# Rear_Motors.net
KiCad netlist of a schematic drawn in Altium Designer
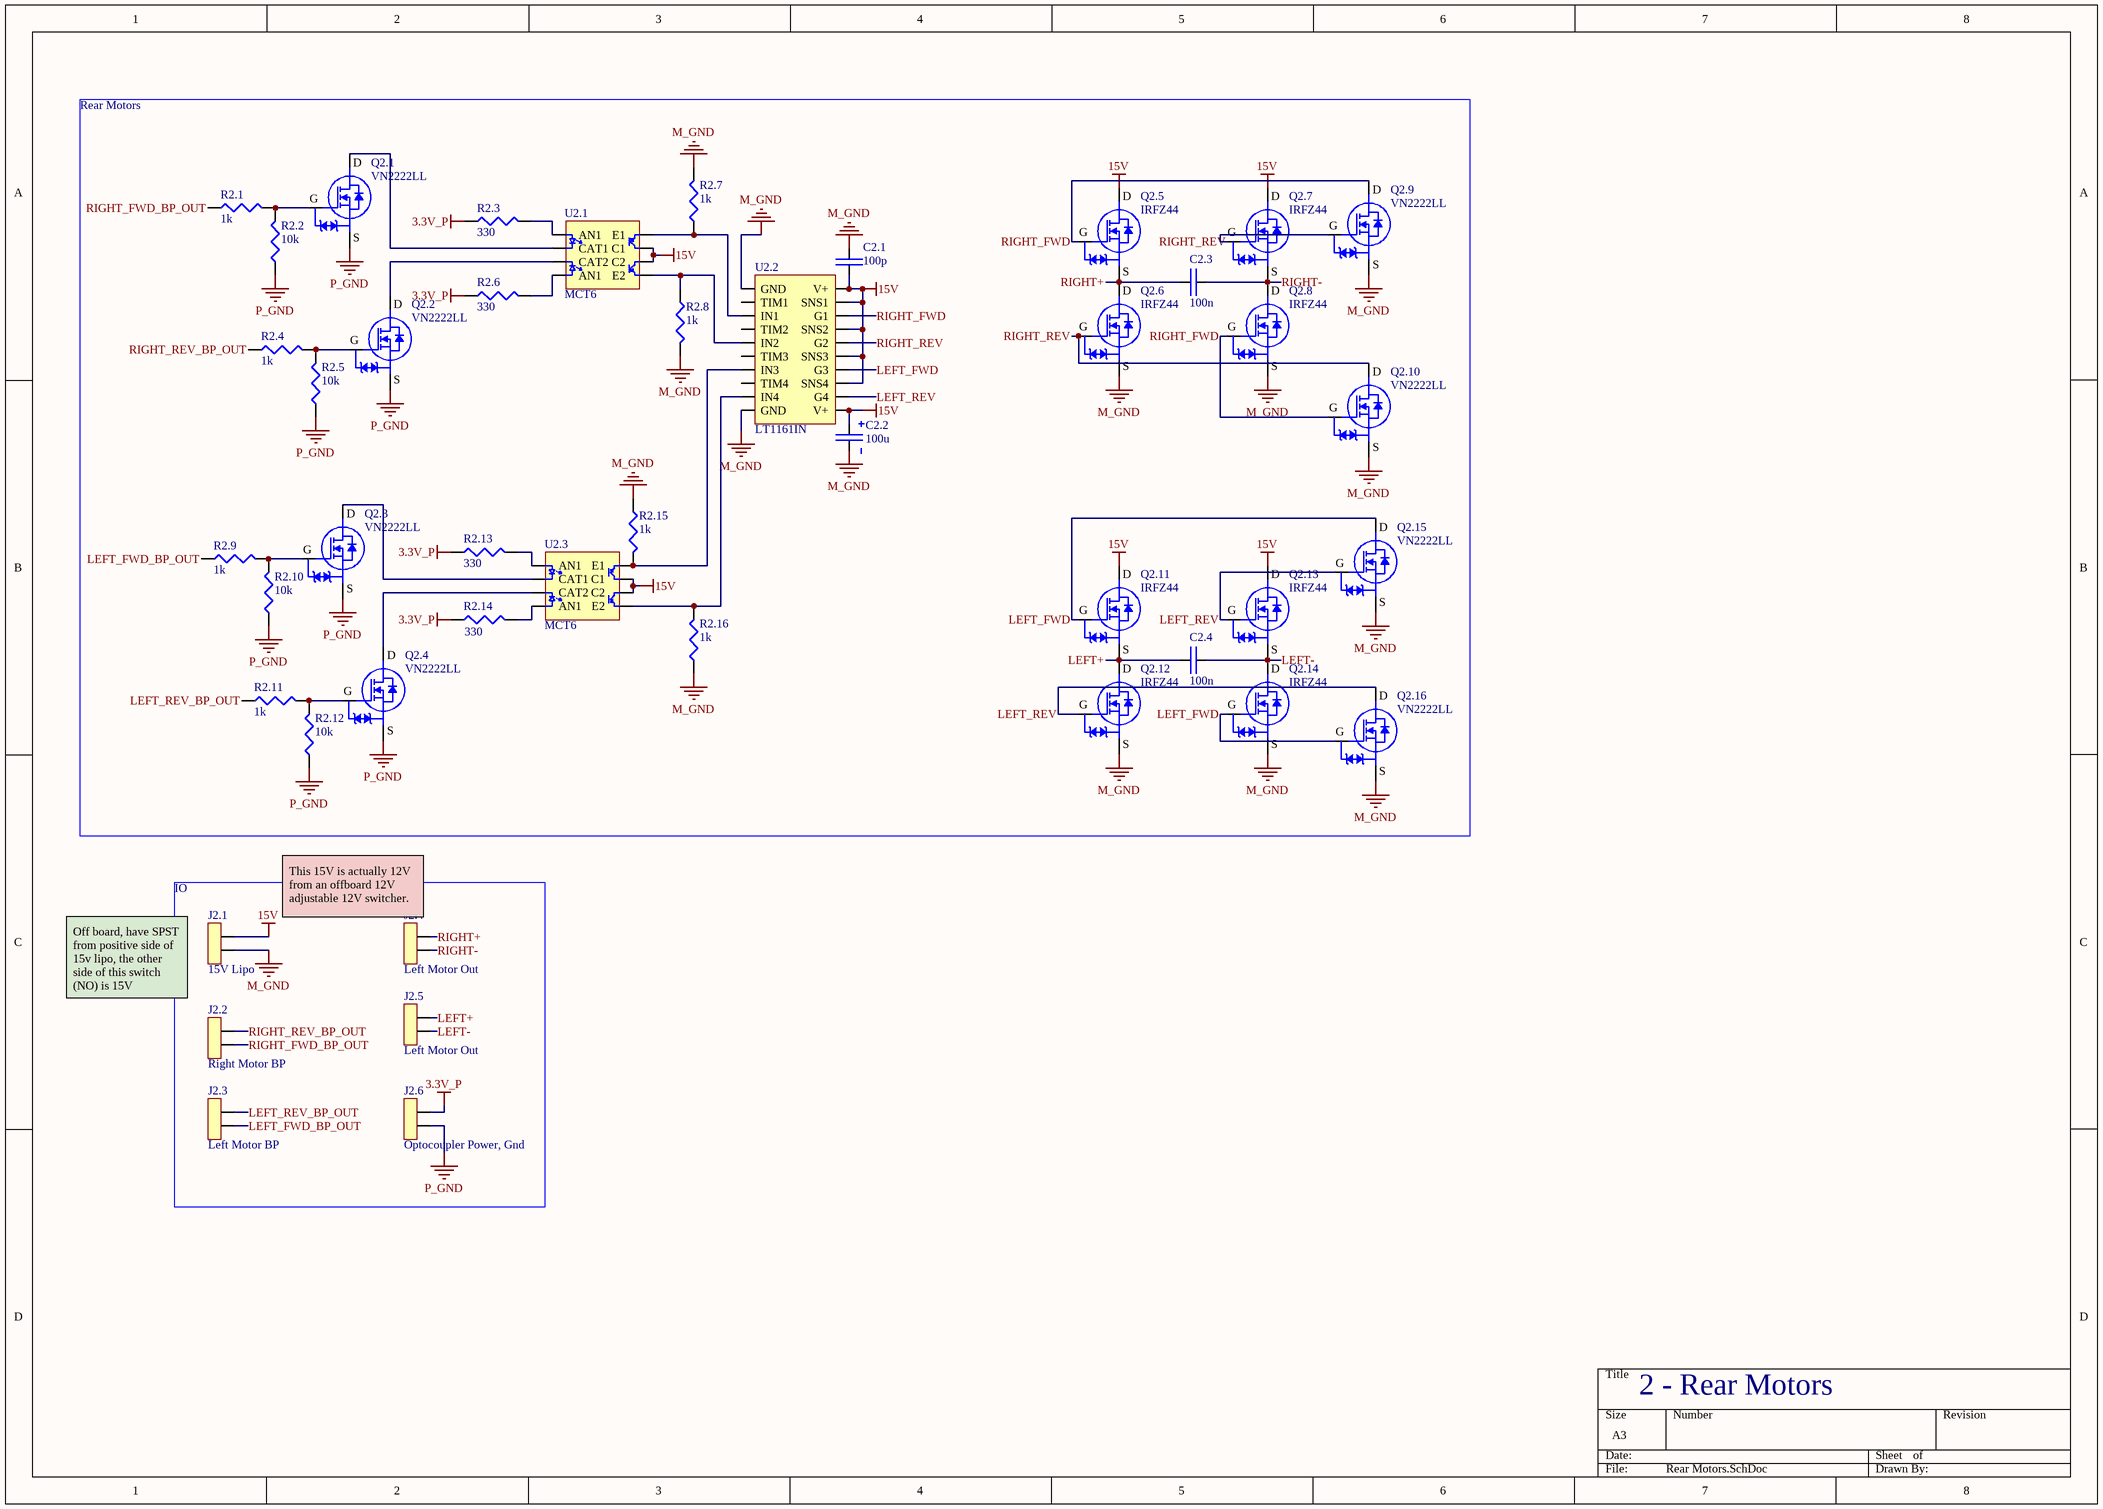
[diagram p0: Rear Motors.SchDoc]

(export (version "E")
  (design (tool "Eeschema 10.0.6"))
  (components
    (comp (ref "C2.1")
      (value "100p")
      (footprint "Non Polarized Cap")
      (libsource (lib "SPICEBot_SchLib") (part "Cap_Generic"))
    )
    (comp (ref "C2.2")
      (value "100u")
      (footprint "Polarized Cap")
      (libsource (lib "SPICEBot_SchLib") (part "Polarized Cap"))
    )
    (comp (ref "C2.3")
      (value "100n")
      (footprint "Non Polarized Cap")
      (libsource (lib "SPICEBot_SchLib") (part "Cap_Generic"))
    )
    (comp (ref "C2.4")
      (value "100n")
      (footprint "Non Polarized Cap")
      (libsource (lib "SPICEBot_SchLib") (part "Cap_Generic"))
    )
    (comp (ref "J2.1")
      (value "15V Lipo")
      (footprint "2pos JST")
      (description "2pos Conn JST")
      (libsource (lib "SPICEBot_SchLib") (part "2pos Conn"))
    )
    (comp (ref "J2.2")
      (value "Right Motor BP")
      (footprint "2pos JST")
      (description "2pos Conn JST")
      (libsource (lib "SPICEBot_SchLib") (part "2pos Conn"))
    )
    (comp (ref "J2.3")
      (value "Left Motor BP")
      (footprint "2pos JST")
      (description "2pos Conn JST")
      (libsource (lib "SPICEBot_SchLib") (part "2pos Conn"))
    )
    (comp (ref "J2.4")
      (value "Left Motor Out")
      (footprint "2pos JST")
      (description "2pos Conn JST")
      (libsource (lib "SPICEBot_SchLib") (part "2pos Conn"))
    )
    (comp (ref "J2.5")
      (value "Left Motor Out")
      (footprint "2pos JST")
      (description "2pos Conn JST")
      (libsource (lib "SPICEBot_SchLib") (part "2pos Conn"))
    )
    (comp (ref "J2.6")
      (value "Optocoupler Power, Gnd")
      (footprint "2pos JST")
      (description "2pos Conn JST")
      (libsource (lib "SPICEBot_SchLib") (part "2pos Conn"))
    )
    (comp (ref "Q2.1")
      (value "VN2222LL")
      (footprint "VN2222LL")
      (description "VN2222LL N-Channel 60 V 150mA 400mW Through Hole TO-92 (TO-226)")
      (libsource (lib "SPICEBot_SchLib") (part "VN2222LL NMOS"))
    )
    (comp (ref "Q2.2")
      (value "VN2222LL")
      (footprint "VN2222LL")
      (description "VN2222LL N-Channel 60 V 150mA 400mW Through Hole TO-92 (TO-226)")
      (libsource (lib "SPICEBot_SchLib") (part "VN2222LL NMOS"))
    )
    (comp (ref "Q2.3")
      (value "VN2222LL")
      (footprint "VN2222LL")
      (description "VN2222LL N-Channel 60 V 150mA 400mW Through Hole TO-92 (TO-226)")
      (libsource (lib "SPICEBot_SchLib") (part "VN2222LL NMOS"))
    )
    (comp (ref "Q2.4")
      (value "VN2222LL")
      (footprint "VN2222LL")
      (description "VN2222LL N-Channel 60 V 150mA 400mW Through Hole TO-92 (TO-226)")
      (libsource (lib "SPICEBot_SchLib") (part "VN2222LL NMOS"))
    )
    (comp (ref "Q2.5")
      (value "IRFZ44")
      (footprint "TO220")
      (description "IRFZ44EPBF N-Channel 60 V 48A 110W Through Hole TO-220AB")
      (libsource (lib "SPICEBot_SchLib") (part "IRFZ44 NMOS"))
    )
    (comp (ref "Q2.6")
      (value "IRFZ44")
      (footprint "TO220")
      (description "IRFZ44EPBF N-Channel 60 V 48A 110W Through Hole TO-220AB")
      (libsource (lib "SPICEBot_SchLib") (part "IRFZ44 NMOS"))
    )
    (comp (ref "Q2.7")
      (value "IRFZ44")
      (footprint "TO220")
      (description "IRFZ44EPBF N-Channel 60 V 48A 110W Through Hole TO-220AB")
      (libsource (lib "SPICEBot_SchLib") (part "IRFZ44 NMOS"))
    )
    (comp (ref "Q2.8")
      (value "IRFZ44")
      (footprint "TO220")
      (description "IRFZ44EPBF N-Channel 60 V 48A 110W Through Hole TO-220AB")
      (libsource (lib "SPICEBot_SchLib") (part "IRFZ44 NMOS"))
    )
    (comp (ref "Q2.9")
      (value "VN2222LL")
      (footprint "VN2222LL")
      (description "VN2222LL N-Channel 60 V 150mA 400mW Through Hole TO-92 (TO-226)")
      (libsource (lib "SPICEBot_SchLib") (part "VN2222LL NMOS"))
    )
    (comp (ref "Q2.10")
      (value "VN2222LL")
      (footprint "VN2222LL")
      (description "VN2222LL N-Channel 60 V 150mA 400mW Through Hole TO-92 (TO-226)")
      (libsource (lib "SPICEBot_SchLib") (part "VN2222LL NMOS"))
    )
    (comp (ref "Q2.11")
      (value "IRFZ44")
      (footprint "TO220")
      (description "IRFZ44EPBF N-Channel 60 V 48A 110W Through Hole TO-220AB")
      (libsource (lib "SPICEBot_SchLib") (part "IRFZ44 NMOS"))
    )
    (comp (ref "Q2.12")
      (value "IRFZ44")
      (footprint "TO220")
      (description "IRFZ44EPBF N-Channel 60 V 48A 110W Through Hole TO-220AB")
      (libsource (lib "SPICEBot_SchLib") (part "IRFZ44 NMOS"))
    )
    (comp (ref "Q2.13")
      (value "IRFZ44")
      (footprint "TO220")
      (description "IRFZ44EPBF N-Channel 60 V 48A 110W Through Hole TO-220AB")
      (libsource (lib "SPICEBot_SchLib") (part "IRFZ44 NMOS"))
    )
    (comp (ref "Q2.14")
      (value "IRFZ44")
      (footprint "TO220")
      (description "IRFZ44EPBF N-Channel 60 V 48A 110W Through Hole TO-220AB")
      (libsource (lib "SPICEBot_SchLib") (part "IRFZ44 NMOS"))
    )
    (comp (ref "Q2.15")
      (value "VN2222LL")
      (footprint "VN2222LL")
      (description "VN2222LL N-Channel 60 V 150mA 400mW Through Hole TO-92 (TO-226)")
      (libsource (lib "SPICEBot_SchLib") (part "VN2222LL NMOS"))
    )
    (comp (ref "Q2.16")
      (value "VN2222LL")
      (footprint "VN2222LL")
      (description "VN2222LL N-Channel 60 V 150mA 400mW Through Hole TO-92 (TO-226)")
      (libsource (lib "SPICEBot_SchLib") (part "VN2222LL NMOS"))
    )
    (comp (ref "R2.1")
      (value "1k")
      (footprint "Res_Generic")
      (libsource (lib "SPICEBot_SchLib") (part "Res_Generic"))
    )
    (comp (ref "R2.2")
      (value "10k")
      (footprint "Res_Generic")
      (libsource (lib "SPICEBot_SchLib") (part "Res_Generic"))
    )
    (comp (ref "R2.3")
      (value "330")
      (footprint "Res_Generic")
      (libsource (lib "SPICEBot_SchLib") (part "Res_Generic"))
    )
    (comp (ref "R2.4")
      (value "1k")
      (footprint "Res_Generic")
      (libsource (lib "SPICEBot_SchLib") (part "Res_Generic"))
    )
    (comp (ref "R2.5")
      (value "10k")
      (footprint "Res_Generic")
      (libsource (lib "SPICEBot_SchLib") (part "Res_Generic"))
    )
    (comp (ref "R2.6")
      (value "330")
      (footprint "Res_Generic")
      (libsource (lib "SPICEBot_SchLib") (part "Res_Generic"))
    )
    (comp (ref "R2.7")
      (value "1k")
      (footprint "Res_Generic")
      (libsource (lib "SPICEBot_SchLib") (part "Res_Generic"))
    )
    (comp (ref "R2.8")
      (value "1k")
      (footprint "Res_Generic")
      (libsource (lib "SPICEBot_SchLib") (part "Res_Generic"))
    )
    (comp (ref "R2.9")
      (value "1k")
      (footprint "Res_Generic")
      (libsource (lib "SPICEBot_SchLib") (part "Res_Generic"))
    )
    (comp (ref "R2.10")
      (value "10k")
      (footprint "Res_Generic")
      (libsource (lib "SPICEBot_SchLib") (part "Res_Generic"))
    )
    (comp (ref "R2.11")
      (value "1k")
      (footprint "Res_Generic")
      (libsource (lib "SPICEBot_SchLib") (part "Res_Generic"))
    )
    (comp (ref "R2.12")
      (value "10k")
      (footprint "Res_Generic")
      (libsource (lib "SPICEBot_SchLib") (part "Res_Generic"))
    )
    (comp (ref "R2.13")
      (value "330")
      (footprint "Res_Generic")
      (libsource (lib "SPICEBot_SchLib") (part "Res_Generic"))
    )
    (comp (ref "R2.14")
      (value "330")
      (footprint "Res_Generic")
      (libsource (lib "SPICEBot_SchLib") (part "Res_Generic"))
    )
    (comp (ref "R2.15")
      (value "1k")
      (footprint "Res_Generic")
      (libsource (lib "SPICEBot_SchLib") (part "Res_Generic"))
    )
    (comp (ref "R2.16")
      (value "1k")
      (footprint "Res_Generic")
      (libsource (lib "SPICEBot_SchLib") (part "Res_Generic"))
    )
    (comp (ref "U2.1")
      (value "MCT6")
      (footprint "DIP8")
      (description "Optoisolator 5.3KV 2CH TRANS 8-DIP")
      (libsource (lib "SPICEBot_SchLib") (part "MCT6 Optocoupler"))
    )
    (comp (ref "U2.2")
      (value "LT1161IN")
      (footprint "DIP20")
      (description "LT1161IN High-Side Gate Driver IC Non-Inverting 20-PDIP")
      (libsource (lib "SPICEBot_SchLib") (part "LT1161IN Gate Driver"))
    )
    (comp (ref "U2.3")
      (value "MCT6")
      (footprint "DIP8")
      (description "Optoisolator 5.3KV 2CH TRANS 8-DIP")
      (libsource (lib "SPICEBot_SchLib") (part "MCT6 Optocoupler"))
    )
  )
  (nets
    (net (code "1") (name "/LEFT+") (class "Default")
      (node (ref "C2.4") (pin "1") (pinfunction "1_1") (pintype "passive"))
      (node (ref "J2.5") (pin "2") (pinfunction "2_2") (pintype "passive"))
      (node (ref "Q2.11") (pin "3") (pinfunction "S_3") (pintype "passive"))
      (node (ref "Q2.12") (pin "2") (pinfunction "D_2") (pintype "passive"))
    )
    (net (code "2") (name "/LEFT-") (class "Default")
      (node (ref "C2.4") (pin "2") (pinfunction "2_2") (pintype "passive"))
      (node (ref "J2.5") (pin "1") (pinfunction "1_1") (pintype "passive"))
      (node (ref "Q2.13") (pin "3") (pinfunction "S_3") (pintype "passive"))
      (node (ref "Q2.14") (pin "2") (pinfunction "D_2") (pintype "passive"))
    )
    (net (code "3") (name "/LEFT_FWD") (class "Default")
      (node (ref "Q2.11") (pin "1") (pinfunction "G_1") (pintype "passive"))
      (node (ref "Q2.14") (pin "1") (pinfunction "G_1") (pintype "passive"))
      (node (ref "Q2.15") (pin "3") (pinfunction "D_3") (pintype "passive"))
      (node (ref "Q2.16") (pin "2") (pinfunction "G_2") (pintype "passive"))
      (node (ref "U2.2") (pin "14") (pinfunction "G3_14") (pintype "passive"))
    )
    (net (code "4") (name "/LEFT_FWD_BP_OUT") (class "Default")
      (node (ref "J2.3") (pin "1") (pinfunction "1_1") (pintype "passive"))
      (node (ref "R2.9") (pin "1") (pinfunction "1_1") (pintype "passive"))
    )
    (net (code "5") (name "/LEFT_REV") (class "Default")
      (node (ref "Q2.12") (pin "1") (pinfunction "G_1") (pintype "passive"))
      (node (ref "Q2.13") (pin "1") (pinfunction "G_1") (pintype "passive"))
      (node (ref "Q2.15") (pin "2") (pinfunction "G_2") (pintype "passive"))
      (node (ref "Q2.16") (pin "3") (pinfunction "D_3") (pintype "passive"))
      (node (ref "U2.2") (pin "12") (pinfunction "G4_12") (pintype "passive"))
    )
    (net (code "6") (name "/LEFT_REV_BP_OUT") (class "Default")
      (node (ref "J2.3") (pin "2") (pinfunction "2_2") (pintype "passive"))
      (node (ref "R2.11") (pin "1") (pinfunction "1_1") (pintype "passive"))
    )
    (net (code "7") (name "/RIGHT+") (class "Default")
      (node (ref "C2.3") (pin "1") (pinfunction "1_1") (pintype "passive"))
      (node (ref "J2.4") (pin "2") (pinfunction "2_2") (pintype "passive"))
      (node (ref "Q2.5") (pin "3") (pinfunction "S_3") (pintype "passive"))
      (node (ref "Q2.6") (pin "2") (pinfunction "D_2") (pintype "passive"))
    )
    (net (code "8") (name "/RIGHT-") (class "Default")
      (node (ref "C2.3") (pin "2") (pinfunction "2_2") (pintype "passive"))
      (node (ref "J2.4") (pin "1") (pinfunction "1_1") (pintype "passive"))
      (node (ref "Q2.7") (pin "3") (pinfunction "S_3") (pintype "passive"))
      (node (ref "Q2.8") (pin "2") (pinfunction "D_2") (pintype "passive"))
    )
    (net (code "9") (name "/RIGHT_FWD") (class "Default")
      (node (ref "Q2.10") (pin "2") (pinfunction "G_2") (pintype "passive"))
      (node (ref "Q2.5") (pin "1") (pinfunction "G_1") (pintype "passive"))
      (node (ref "Q2.8") (pin "1") (pinfunction "G_1") (pintype "passive"))
      (node (ref "Q2.9") (pin "3") (pinfunction "D_3") (pintype "passive"))
      (node (ref "U2.2") (pin "18") (pinfunction "G1_18") (pintype "passive"))
    )
    (net (code "10") (name "/RIGHT_FWD_BP_OUT") (class "Default")
      (node (ref "J2.2") (pin "1") (pinfunction "1_1") (pintype "passive"))
      (node (ref "R2.1") (pin "1") (pinfunction "1_1") (pintype "passive"))
    )
    (net (code "11") (name "/RIGHT_REV") (class "Default")
      (node (ref "Q2.10") (pin "3") (pinfunction "D_3") (pintype "passive"))
      (node (ref "Q2.6") (pin "1") (pinfunction "G_1") (pintype "passive"))
      (node (ref "Q2.7") (pin "1") (pinfunction "G_1") (pintype "passive"))
      (node (ref "Q2.9") (pin "2") (pinfunction "G_2") (pintype "passive"))
      (node (ref "U2.2") (pin "16") (pinfunction "G2_16") (pintype "passive"))
    )
    (net (code "12") (name "/RIGHT_REV_BP_OUT") (class "Default")
      (node (ref "J2.2") (pin "2") (pinfunction "2_2") (pintype "passive"))
      (node (ref "R2.4") (pin "1") (pinfunction "1_1") (pintype "passive"))
    )
    (net (code "13") (name "3.3V_P") (class "Default")
      (node (ref "J2.6") (pin "2") (pinfunction "2_2") (pintype "passive"))
      (node (ref "R2.13") (pin "1") (pinfunction "1_1") (pintype "passive"))
      (node (ref "R2.14") (pin "1") (pinfunction "1_1") (pintype "passive"))
      (node (ref "R2.3") (pin "1") (pinfunction "1_1") (pintype "passive"))
      (node (ref "R2.6") (pin "1") (pinfunction "1_1") (pintype "passive"))
    )
    (net (code "14") (name "15V") (class "Default")
      (node (ref "C2.1") (pin "1") (pinfunction "1_1") (pintype "passive"))
      (node (ref "C2.2") (pin "1") (pinfunction "1_1") (pintype "passive"))
      (node (ref "J2.1") (pin "2") (pinfunction "2_2") (pintype "passive"))
      (node (ref "Q2.11") (pin "2") (pinfunction "D_2") (pintype "passive"))
      (node (ref "Q2.13") (pin "2") (pinfunction "D_2") (pintype "passive"))
      (node (ref "Q2.5") (pin "2") (pinfunction "D_2") (pintype "passive"))
      (node (ref "Q2.7") (pin "2") (pinfunction "D_2") (pintype "passive"))
      (node (ref "U2.1") (pin "6") (pinfunction "C2_6") (pintype "passive"))
      (node (ref "U2.1") (pin "7") (pinfunction "C1_7") (pintype "passive"))
      (node (ref "U2.2") (pin "11") (pinfunction "V+_11") (pintype "passive"))
      (node (ref "U2.2") (pin "13") (pinfunction "SNS4_13") (pintype "passive"))
      (node (ref "U2.2") (pin "15") (pinfunction "SNS3_15") (pintype "passive"))
      (node (ref "U2.2") (pin "17") (pinfunction "SNS2_17") (pintype "passive"))
      (node (ref "U2.2") (pin "19") (pinfunction "SNS1_19") (pintype "passive"))
      (node (ref "U2.2") (pin "20") (pinfunction "V+_20") (pintype "passive"))
      (node (ref "U2.3") (pin "6") (pinfunction "C2_6") (pintype "passive"))
      (node (ref "U2.3") (pin "7") (pinfunction "C1_7") (pintype "passive"))
    )
    (net (code "15") (name "M_GND") (class "Default")
      (node (ref "C2.1") (pin "2") (pinfunction "2_2") (pintype "passive"))
      (node (ref "C2.2") (pin "2") (pinfunction "2_2") (pintype "passive"))
      (node (ref "J2.1") (pin "1") (pinfunction "1_1") (pintype "passive"))
      (node (ref "Q2.10") (pin "1") (pinfunction "S_1") (pintype "passive"))
      (node (ref "Q2.12") (pin "3") (pinfunction "S_3") (pintype "passive"))
      (node (ref "Q2.14") (pin "3") (pinfunction "S_3") (pintype "passive"))
      (node (ref "Q2.15") (pin "1") (pinfunction "S_1") (pintype "passive"))
      (node (ref "Q2.16") (pin "1") (pinfunction "S_1") (pintype "passive"))
      (node (ref "Q2.6") (pin "3") (pinfunction "S_3") (pintype "passive"))
      (node (ref "Q2.8") (pin "3") (pinfunction "S_3") (pintype "passive"))
      (node (ref "Q2.9") (pin "1") (pinfunction "S_1") (pintype "passive"))
      (node (ref "R2.15") (pin "1") (pinfunction "1_1") (pintype "passive"))
      (node (ref "R2.16") (pin "1") (pinfunction "1_1") (pintype "passive"))
      (node (ref "R2.7") (pin "2") (pinfunction "2_2") (pintype "passive"))
      (node (ref "R2.8") (pin "2") (pinfunction "2_2") (pintype "passive"))
      (node (ref "U2.2") (pin "1") (pinfunction "GND_1") (pintype "passive"))
      (node (ref "U2.2") (pin "10") (pinfunction "GND_10") (pintype "passive"))
    )
    (net (code "16") (name "Net-(Q2.1-D)") (class "Default")
      (node (ref "Q2.1") (pin "3") (pinfunction "D_3") (pintype "passive"))
      (node (ref "U2.1") (pin "2") (pinfunction "CAT1_2") (pintype "passive"))
    )
    (net (code "17") (name "Net-(Q2.1-G)") (class "Default")
      (node (ref "Q2.1") (pin "2") (pinfunction "G_2") (pintype "passive"))
      (node (ref "R2.1") (pin "2") (pinfunction "2_2") (pintype "passive"))
      (node (ref "R2.2") (pin "2") (pinfunction "2_2") (pintype "passive"))
    )
    (net (code "18") (name "Net-(Q2.2-D)") (class "Default")
      (node (ref "Q2.2") (pin "3") (pinfunction "D_3") (pintype "passive"))
      (node (ref "U2.1") (pin "3") (pinfunction "CAT2_3") (pintype "passive"))
    )
    (net (code "19") (name "Net-(Q2.2-G)") (class "Default")
      (node (ref "Q2.2") (pin "2") (pinfunction "G_2") (pintype "passive"))
      (node (ref "R2.4") (pin "2") (pinfunction "2_2") (pintype "passive"))
      (node (ref "R2.5") (pin "2") (pinfunction "2_2") (pintype "passive"))
    )
    (net (code "20") (name "Net-(Q2.3-D)") (class "Default")
      (node (ref "Q2.3") (pin "3") (pinfunction "D_3") (pintype "passive"))
      (node (ref "U2.3") (pin "2") (pinfunction "CAT1_2") (pintype "passive"))
    )
    (net (code "21") (name "Net-(Q2.3-G)") (class "Default")
      (node (ref "Q2.3") (pin "2") (pinfunction "G_2") (pintype "passive"))
      (node (ref "R2.10") (pin "2") (pinfunction "2_2") (pintype "passive"))
      (node (ref "R2.9") (pin "2") (pinfunction "2_2") (pintype "passive"))
    )
    (net (code "22") (name "Net-(Q2.4-D)") (class "Default")
      (node (ref "Q2.4") (pin "3") (pinfunction "D_3") (pintype "passive"))
      (node (ref "U2.3") (pin "3") (pinfunction "CAT2_3") (pintype "passive"))
    )
    (net (code "23") (name "Net-(Q2.4-G)") (class "Default")
      (node (ref "Q2.4") (pin "2") (pinfunction "G_2") (pintype "passive"))
      (node (ref "R2.11") (pin "2") (pinfunction "2_2") (pintype "passive"))
      (node (ref "R2.12") (pin "2") (pinfunction "2_2") (pintype "passive"))
    )
    (net (code "24") (name "Net-(R2.3-Pad2)") (class "Default")
      (node (ref "R2.3") (pin "2") (pinfunction "2_2") (pintype "passive"))
      (node (ref "U2.1") (pin "1") (pinfunction "AN1_1") (pintype "passive"))
    )
    (net (code "25") (name "Net-(R2.6-Pad2)") (class "Default")
      (node (ref "R2.6") (pin "2") (pinfunction "2_2") (pintype "passive"))
      (node (ref "U2.1") (pin "4") (pinfunction "AN1_4") (pintype "passive"))
    )
    (net (code "26") (name "Net-(R2.13-Pad2)") (class "Default")
      (node (ref "R2.13") (pin "2") (pinfunction "2_2") (pintype "passive"))
      (node (ref "U2.3") (pin "1") (pinfunction "AN1_1") (pintype "passive"))
    )
    (net (code "27") (name "Net-(R2.14-Pad2)") (class "Default")
      (node (ref "R2.14") (pin "2") (pinfunction "2_2") (pintype "passive"))
      (node (ref "U2.3") (pin "4") (pinfunction "AN1_4") (pintype "passive"))
    )
    (net (code "28") (name "Net-(U2.1-E1)") (class "Default")
      (node (ref "R2.7") (pin "1") (pinfunction "1_1") (pintype "passive"))
      (node (ref "U2.1") (pin "8") (pinfunction "E1_8") (pintype "passive"))
      (node (ref "U2.2") (pin "3") (pinfunction "IN1_3") (pintype "passive"))
    )
    (net (code "29") (name "Net-(U2.1-E2)") (class "Default")
      (node (ref "R2.8") (pin "1") (pinfunction "1_1") (pintype "passive"))
      (node (ref "U2.1") (pin "5") (pinfunction "E2_5") (pintype "passive"))
      (node (ref "U2.2") (pin "5") (pinfunction "IN2_5") (pintype "passive"))
    )
    (net (code "30") (name "Net-(U2.2-IN3)") (class "Default")
      (node (ref "R2.15") (pin "2") (pinfunction "2_2") (pintype "passive"))
      (node (ref "U2.2") (pin "7") (pinfunction "IN3_7") (pintype "passive"))
      (node (ref "U2.3") (pin "8") (pinfunction "E1_8") (pintype "passive"))
    )
    (net (code "31") (name "Net-(U2.2-IN4)") (class "Default")
      (node (ref "R2.16") (pin "2") (pinfunction "2_2") (pintype "passive"))
      (node (ref "U2.2") (pin "9") (pinfunction "IN4_9") (pintype "passive"))
      (node (ref "U2.3") (pin "5") (pinfunction "E2_5") (pintype "passive"))
    )
    (net (code "32") (name "P_GND") (class "Default")
      (node (ref "J2.6") (pin "1") (pinfunction "1_1") (pintype "passive"))
      (node (ref "Q2.1") (pin "1") (pinfunction "S_1") (pintype "passive"))
      (node (ref "Q2.2") (pin "1") (pinfunction "S_1") (pintype "passive"))
      (node (ref "Q2.3") (pin "1") (pinfunction "S_1") (pintype "passive"))
      (node (ref "Q2.4") (pin "1") (pinfunction "S_1") (pintype "passive"))
      (node (ref "R2.10") (pin "1") (pinfunction "1_1") (pintype "passive"))
      (node (ref "R2.12") (pin "1") (pinfunction "1_1") (pintype "passive"))
      (node (ref "R2.2") (pin "1") (pinfunction "1_1") (pintype "passive"))
      (node (ref "R2.5") (pin "1") (pinfunction "1_1") (pintype "passive"))
    )
    (net (code "33") (name "unconnected-(U2.2-TIM1-Pad2)") (class "Default")
      (node (ref "U2.2") (pin "2") (pinfunction "TIM1_2") (pintype "passive"))
    )
    (net (code "34") (name "unconnected-(U2.2-TIM2-Pad4)") (class "Default")
      (node (ref "U2.2") (pin "4") (pinfunction "TIM2_4") (pintype "passive"))
    )
    (net (code "35") (name "unconnected-(U2.2-TIM3-Pad6)") (class "Default")
      (node (ref "U2.2") (pin "6") (pinfunction "TIM3_6") (pintype "passive"))
    )
    (net (code "36") (name "unconnected-(U2.2-TIM4-Pad8)") (class "Default")
      (node (ref "U2.2") (pin "8") (pinfunction "TIM4_8") (pintype "passive"))
    )
  )
)
